# MEZ_IC.net
KiCad netlist of a schematic drawn in Altium Designer
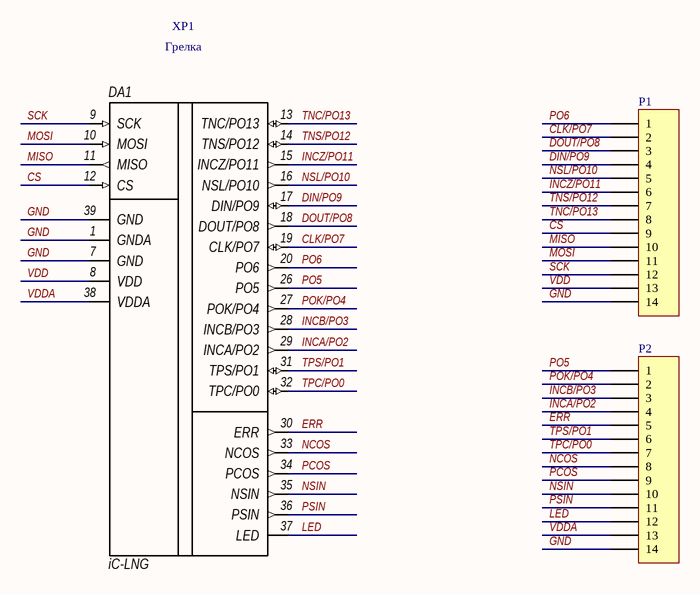
[diagram p0: MEZ_IC.SchDoc]

(export (version "E")
  (design (tool "Eeschema 10.0.6"))
  (components
    (comp (ref "DA1")
      (value "iC-LNG")
      (footprint "iC-LNG oQFN")
      (description "Оптический энкодер")
      (libsource (lib "VPL") (part "iC-LNG"))
    )
    (comp (ref "P1")
      (value "Header 14")
      (footprint "HDR1X14")
      (description "Header, 14-Pin")
      (fields (field (name "PUBLISHER") "Altium Limited"))
      (libsource (lib "Miscellaneous Connectors") (part "Header 14"))
    )
    (comp (ref "P2")
      (value "Header 14")
      (footprint "HDR1X14")
      (description "Header, 14-Pin")
      (fields (field (name "PUBLISHER") "Altium Limited"))
      (libsource (lib "Miscellaneous Connectors") (part "Header 14"))
    )
    (comp (ref "XP1") (value "Грелка") (footprint "Грелка") (libsource (lib "VPL") (part "Грелка")))
  )
  (nets
    (net (code "1") (name "/CLK{slash}PO7") (class "Default")
      (node (ref "DA1") (pin "19") (pinfunction "CLK/PO7_19") (pintype "bidirectional"))
      (node (ref "P1") (pin "2") (pinfunction "2_2") (pintype "passive"))
    )
    (net (code "2") (name "/CS") (class "Default")
      (node (ref "DA1") (pin "12") (pinfunction "CS_12") (pintype "input"))
      (node (ref "P1") (pin "9") (pinfunction "9_9") (pintype "passive"))
    )
    (net (code "3") (name "/DIN{slash}PO9") (class "Default")
      (node (ref "DA1") (pin "17") (pinfunction "DIN/PO9_17") (pintype "bidirectional"))
      (node (ref "P1") (pin "4") (pinfunction "4_4") (pintype "passive"))
    )
    (net (code "4") (name "/DOUT{slash}PO8") (class "Default")
      (node (ref "DA1") (pin "18") (pinfunction "DOUT/PO8_18") (pintype "output"))
      (node (ref "P1") (pin "3") (pinfunction "3_3") (pintype "passive"))
    )
    (net (code "5") (name "/ERR") (class "Default")
      (node (ref "DA1") (pin "30") (pinfunction "ERR_30") (pintype "output"))
      (node (ref "P2") (pin "5") (pinfunction "5_5") (pintype "passive"))
    )
    (net (code "6") (name "/GND") (class "Default")
      (node (ref "DA1") (pin "1") (pinfunction "GNDA_1") (pintype "power_in"))
      (node (ref "DA1") (pin "39") (pinfunction "GND_39") (pintype "passive"))
      (node (ref "DA1") (pin "7") (pinfunction "GND_7") (pintype "power_in"))
      (node (ref "P1") (pin "14") (pinfunction "14_14") (pintype "passive"))
      (node (ref "P2") (pin "14") (pinfunction "14_14") (pintype "passive"))
    )
    (net (code "7") (name "/INCA{slash}PO2") (class "Default")
      (node (ref "DA1") (pin "29") (pinfunction "INCA/PO2_29") (pintype "output"))
      (node (ref "P2") (pin "4") (pinfunction "4_4") (pintype "passive"))
    )
    (net (code "8") (name "/INCB{slash}PO3") (class "Default")
      (node (ref "DA1") (pin "28") (pinfunction "INCB/PO3_28") (pintype "output"))
      (node (ref "P2") (pin "3") (pinfunction "3_3") (pintype "passive"))
    )
    (net (code "9") (name "/INCZ{slash}PO11") (class "Default")
      (node (ref "DA1") (pin "15") (pinfunction "INCZ/PO11_15") (pintype "output"))
      (node (ref "P1") (pin "6") (pinfunction "6_6") (pintype "passive"))
    )
    (net (code "10") (name "/LED") (class "Default")
      (node (ref "DA1") (pin "37") (pinfunction "LED_37") (pintype "power_in"))
      (node (ref "P2") (pin "12") (pinfunction "12_12") (pintype "passive"))
    )
    (net (code "11") (name "/MISO") (class "Default")
      (node (ref "DA1") (pin "11") (pinfunction "MISO_11") (pintype "output"))
      (node (ref "P1") (pin "10") (pinfunction "10_10") (pintype "passive"))
    )
    (net (code "12") (name "/MOSI") (class "Default")
      (node (ref "DA1") (pin "10") (pinfunction "MOSI_10") (pintype "input"))
      (node (ref "P1") (pin "11") (pinfunction "11_11") (pintype "passive"))
    )
    (net (code "13") (name "/NCOS") (class "Default")
      (node (ref "DA1") (pin "33") (pinfunction "NCOS_33") (pintype "output"))
      (node (ref "P2") (pin "8") (pinfunction "8_8") (pintype "passive"))
    )
    (net (code "14") (name "/NSIN") (class "Default")
      (node (ref "DA1") (pin "35") (pinfunction "NSIN_35") (pintype "output"))
      (node (ref "P2") (pin "10") (pinfunction "10_10") (pintype "passive"))
    )
    (net (code "15") (name "/NSL{slash}PO10") (class "Default")
      (node (ref "DA1") (pin "16") (pinfunction "NSL/PO10_16") (pintype "output"))
      (node (ref "P1") (pin "5") (pinfunction "5_5") (pintype "passive"))
    )
    (net (code "16") (name "/PCOS") (class "Default")
      (node (ref "DA1") (pin "34") (pinfunction "PCOS_34") (pintype "output"))
      (node (ref "P2") (pin "9") (pinfunction "9_9") (pintype "passive"))
    )
    (net (code "17") (name "/PO5") (class "Default")
      (node (ref "DA1") (pin "26") (pinfunction "PO5_26") (pintype "output"))
      (node (ref "P2") (pin "1") (pinfunction "1_1") (pintype "passive"))
    )
    (net (code "18") (name "/PO6") (class "Default")
      (node (ref "DA1") (pin "20") (pinfunction "PO6_20") (pintype "output"))
      (node (ref "P1") (pin "1") (pinfunction "1_1") (pintype "passive"))
    )
    (net (code "19") (name "/POK{slash}PO4") (class "Default")
      (node (ref "DA1") (pin "27") (pinfunction "POK/PO4_27") (pintype "output"))
      (node (ref "P2") (pin "2") (pinfunction "2_2") (pintype "passive"))
    )
    (net (code "20") (name "/PSIN") (class "Default")
      (node (ref "DA1") (pin "36") (pinfunction "PSIN_36") (pintype "output"))
      (node (ref "P2") (pin "11") (pinfunction "11_11") (pintype "passive"))
    )
    (net (code "21") (name "/SCK") (class "Default")
      (node (ref "DA1") (pin "9") (pinfunction "SCK_9") (pintype "input"))
      (node (ref "P1") (pin "12") (pinfunction "12_12") (pintype "passive"))
    )
    (net (code "22") (name "/TNC{slash}PO13") (class "Default")
      (node (ref "DA1") (pin "13") (pinfunction "TNC/PO13_13") (pintype "bidirectional"))
      (node (ref "P1") (pin "8") (pinfunction "8_8") (pintype "passive"))
    )
    (net (code "23") (name "/TNS{slash}PO12") (class "Default")
      (node (ref "DA1") (pin "14") (pinfunction "TNS/PO12_14") (pintype "bidirectional"))
      (node (ref "P1") (pin "7") (pinfunction "7_7") (pintype "passive"))
    )
    (net (code "24") (name "/TPC{slash}PO0") (class "Default")
      (node (ref "DA1") (pin "32") (pinfunction "TPC/PO0_32") (pintype "bidirectional"))
      (node (ref "P2") (pin "7") (pinfunction "7_7") (pintype "passive"))
    )
    (net (code "25") (name "/TPS{slash}PO1") (class "Default")
      (node (ref "DA1") (pin "31") (pinfunction "TPS/PO1_31") (pintype "bidirectional"))
      (node (ref "P2") (pin "6") (pinfunction "6_6") (pintype "passive"))
    )
    (net (code "26") (name "/VDD") (class "Default")
      (node (ref "DA1") (pin "8") (pinfunction "VDD_8") (pintype "power_in"))
      (node (ref "P1") (pin "13") (pinfunction "13_13") (pintype "passive"))
    )
    (net (code "27") (name "/VDDA") (class "Default")
      (node (ref "DA1") (pin "38") (pinfunction "VDDA_38") (pintype "power_in"))
      (node (ref "P2") (pin "13") (pinfunction "13_13") (pintype "passive"))
    )
  )
)
